# karmanDB_power.net
KiCad netlist of a schematic drawn in Altium Designer
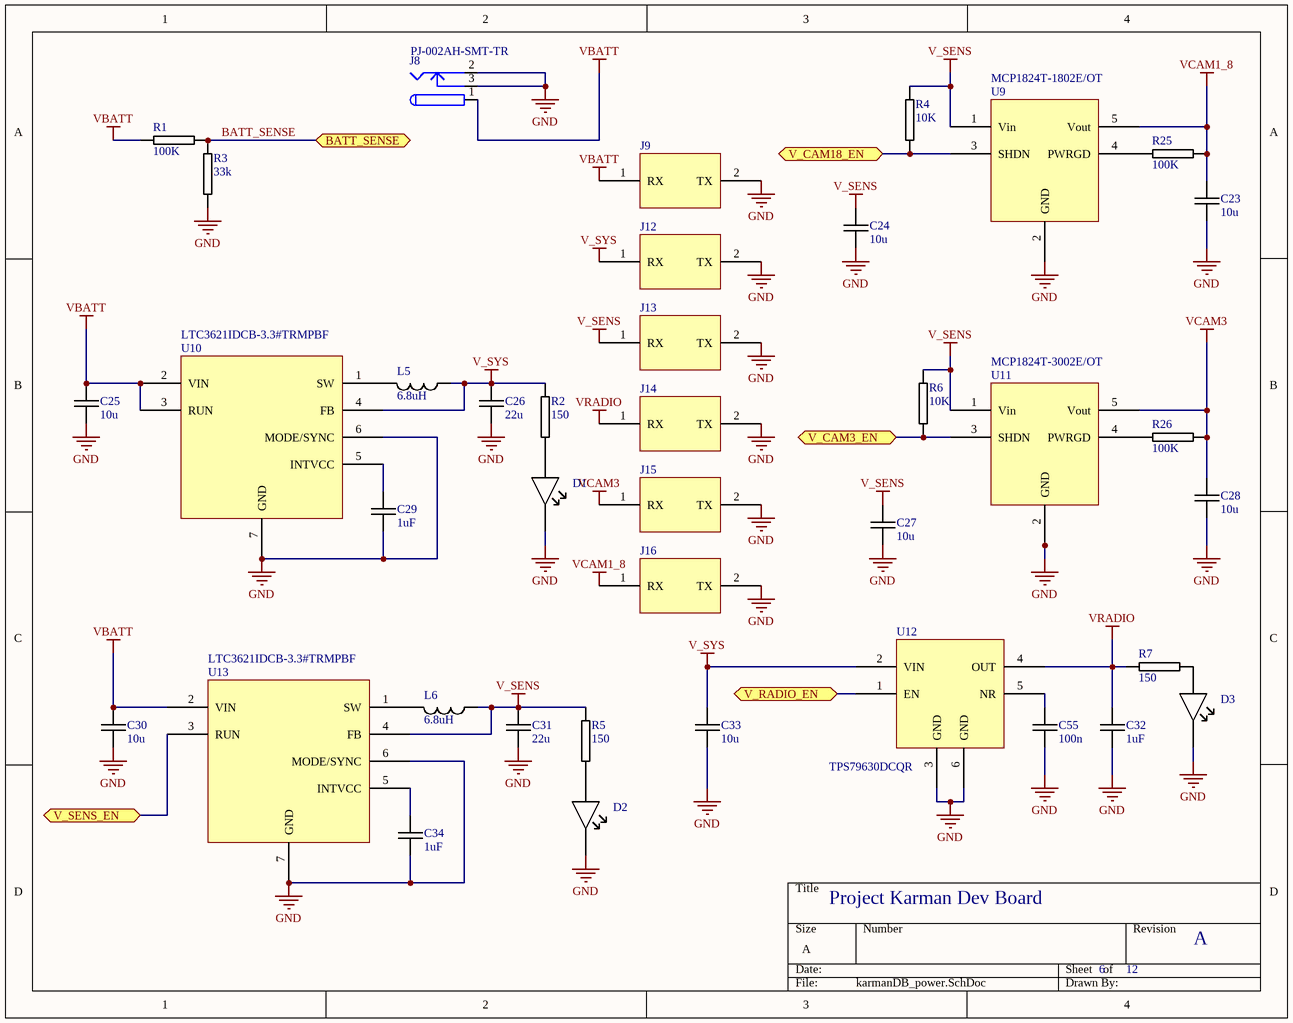
[diagram p0: karmanDB_power.SchDoc]

(export (version "E")
  (design (tool "Eeschema 10.0.6"))
  (components
    (comp (ref "C23")
      (value "10u")
      (footprint "MURATA_GRM_0603")
      (description "CAP CER 10UF 6.3V 20% X5R 0603")
      (fields
        (field (name "MANUFACTURER") "Murata Electronics North America")
        (field (name "MANUFACTURER PART NUMBER") "GRM188R60J106ME47J")
      )
      (libsource (lib "project_symbols") (part "CAP_MURATA_GRM188R60J106"))
    )
    (comp (ref "C24")
      (value "10u")
      (footprint "MURATA_GRM_0603")
      (description "CAP CER 10UF 6.3V 20% X5R 0603")
      (fields
        (field (name "MANUFACTURER") "Murata Electronics North America")
        (field (name "MANUFACTURER PART NUMBER") "GRM188R60J106ME47J")
      )
      (libsource (lib "project_symbols") (part "CAP_MURATA_GRM188R60J106"))
    )
    (comp (ref "C25")
      (value "10u")
      (footprint "MURATA_GRM_0603")
      (description "CAP CER 10UF 6.3V 20% X5R 0603")
      (fields
        (field (name "MANUFACTURER") "Murata Electronics North America")
        (field (name "MANUFACTURER PART NUMBER") "GRM188R60J106ME47J")
      )
      (libsource (lib "project_symbols") (part "CAP_MURATA_GRM188R60J106"))
    )
    (comp (ref "C26")
      (value "22u")
      (footprint "MURATA_GRM_0603")
      (description "CAP CER 22UF 10V 20% X5R 0603")
      (fields
        (field (name "MANUFACTURER") "Murata Electronics North America")
        (field (name "MANUFACTURER PART NUMBER") "GRM188R61A226ME15D")
      )
      (libsource (lib "project_symbols") (part "CAP_MURATA_GRM188R61A226ME15D"))
    )
    (comp (ref "C27")
      (value "10u")
      (footprint "MURATA_GRM_0603")
      (description "CAP CER 10UF 6.3V 20% X5R 0603")
      (fields
        (field (name "MANUFACTURER") "Murata Electronics North America")
        (field (name "MANUFACTURER PART NUMBER") "GRM188R60J106ME47J")
      )
      (libsource (lib "project_symbols") (part "CAP_MURATA_GRM188R60J106"))
    )
    (comp (ref "C28")
      (value "10u")
      (footprint "MURATA_GRM_0603")
      (description "CAP CER 10UF 6.3V 20% X5R 0603")
      (fields
        (field (name "MANUFACTURER") "Murata Electronics North America")
        (field (name "MANUFACTURER PART NUMBER") "GRM188R60J106ME47J")
      )
      (libsource (lib "project_symbols") (part "CAP_MURATA_GRM188R60J106"))
    )
    (comp (ref "C29")
      (value "1uF")
      (footprint "MURATA_GRM_0402")
      (description "CAP CER 1uF 10volts X5R 10% 0402")
      (fields
        (field (name "MANUFACTURER") "Murata Electronics")
        (field (name "MANUFACTURER PART NUMBER") "GRM155R61A105KE15D")
      )
      (libsource (lib "project_symbols") (part "CAP_MURATA_GRM155R61A105KE15D"))
    )
    (comp (ref "C30")
      (value "10u")
      (footprint "MURATA_GRM_0603")
      (description "CAP CER 10UF 6.3V 20% X5R 0603")
      (fields
        (field (name "MANUFACTURER") "Murata Electronics North America")
        (field (name "MANUFACTURER PART NUMBER") "GRM188R60J106ME47J")
      )
      (libsource (lib "project_symbols") (part "CAP_MURATA_GRM188R60J106"))
    )
    (comp (ref "C31")
      (value "22u")
      (footprint "MURATA_GRM_0603")
      (description "CAP CER 22UF 10V 20% X5R 0603")
      (fields
        (field (name "MANUFACTURER") "Murata Electronics North America")
        (field (name "MANUFACTURER PART NUMBER") "GRM188R61A226ME15D")
      )
      (libsource (lib "project_symbols") (part "CAP_MURATA_GRM188R61A226ME15D"))
    )
    (comp (ref "C32")
      (value "1uF")
      (footprint "MURATA_GRM_0402")
      (description "CAP CER 1uF 10volts X5R 10% 0402")
      (fields
        (field (name "MANUFACTURER") "Murata Electronics")
        (field (name "MANUFACTURER PART NUMBER") "GRM155R61A105KE15D")
      )
      (libsource (lib "project_symbols") (part "CAP_MURATA_GRM155R61A105KE15D"))
    )
    (comp (ref "C33")
      (value "10u")
      (footprint "MURATA_GRM_0603")
      (description "CAP CER 10UF 6.3V 20% X5R 0603")
      (fields
        (field (name "MANUFACTURER") "Murata Electronics North America")
        (field (name "MANUFACTURER PART NUMBER") "GRM188R60J106ME47J")
      )
      (libsource (lib "project_symbols") (part "CAP_MURATA_GRM188R60J106"))
    )
    (comp (ref "C34")
      (value "1uF")
      (footprint "MURATA_GRM_0402")
      (description "CAP CER 1uF 10volts X5R 10% 0402")
      (fields
        (field (name "MANUFACTURER") "Murata Electronics")
        (field (name "MANUFACTURER PART NUMBER") "GRM155R61A105KE15D")
      )
      (libsource (lib "project_symbols") (part "CAP_MURATA_GRM155R61A105KE15D"))
    )
    (comp (ref "C55")
      (value "100n")
      (footprint "MURATA_GRM_0603")
      (description "CAP CER 0.1UF 6.3V 10% X7R 0603")
      (fields
        (field (name "MANUFACTURER") "Murata Electronics North America")
        (field (name "MANUFACTURER PART NUMBER") "GRM188R70J104KA01D")
      )
      (libsource (lib "project_symbols") (part "CAP_MURATA_GRM188R70J104KA01D"))
    )
    (comp (ref "D1")
      (value "LED_LITEON_LTST-C150CKT")
      (footprint "LITEON_LTST-C150")
      (description "LED RED CLEAR 1206 SMD")
      (fields
        (field (name "MANUFACTURER") "Lite-On Inc")
        (field (name "MANUFACTURER PART NUMBER") "LTST-C150CKT")
      )
      (libsource (lib "project_symbols") (part "LED_LITEON_LTST-C150CKT"))
    )
    (comp (ref "D2")
      (value "LED_LITEON_LTST-C150CKT")
      (footprint "LITEON_LTST-C150")
      (description "LED RED CLEAR 1206 SMD")
      (fields
        (field (name "MANUFACTURER") "Lite-On Inc")
        (field (name "MANUFACTURER PART NUMBER") "LTST-C150CKT")
      )
      (libsource (lib "project_symbols") (part "LED_LITEON_LTST-C150CKT"))
    )
    (comp (ref "D3")
      (value "LED_LITEON_LTST-C150CKT")
      (footprint "LITEON_LTST-C150")
      (description "LED RED CLEAR 1206 SMD")
      (fields
        (field (name "MANUFACTURER") "Lite-On Inc")
        (field (name "MANUFACTURER PART NUMBER") "LTST-C150CKT")
      )
      (libsource (lib "project_symbols") (part "LED_LITEON_LTST-C150CKT"))
    )
    (comp (ref "J8")
      (value "PJ-002AH-SMT-TR")
      (footprint "PJ-002AH-SMT")
      (description "CONN POWER JACK 2.1X5.5MM HI CUR")
      (fields (field (name "MANUFACTURER") "CUI Inc."))
      (libsource (lib "karman_pcb") (part "PJ-002AH-SMT-TR"))
    )
    (comp (ref "J9")
      (value "961102-6404-AR")
      (footprint "3M_961102-6X04")
      (description "CONN HEADER VERT SGL 2POS GOLD")
      (fields (field (name "MANUFACTURER") "3M"))
      (libsource (lib "karman_pcb") (part "961102-6404-AR"))
    )
    (comp (ref "J12")
      (value "961102-6404-AR")
      (footprint "3M_961102-6X04")
      (description "CONN HEADER VERT SGL 2POS GOLD")
      (fields (field (name "MANUFACTURER") "3M"))
      (libsource (lib "karman_pcb") (part "961102-6404-AR"))
    )
    (comp (ref "J13")
      (value "961102-6404-AR")
      (footprint "3M_961102-6X04")
      (description "CONN HEADER VERT SGL 2POS GOLD")
      (fields (field (name "MANUFACTURER") "3M"))
      (libsource (lib "karman_pcb") (part "961102-6404-AR"))
    )
    (comp (ref "J14")
      (value "961102-6404-AR")
      (footprint "3M_961102-6X04")
      (description "CONN HEADER VERT SGL 2POS GOLD")
      (fields (field (name "MANUFACTURER") "3M"))
      (libsource (lib "karman_pcb") (part "961102-6404-AR"))
    )
    (comp (ref "J15")
      (value "961102-6404-AR")
      (footprint "3M_961102-6X04")
      (description "CONN HEADER VERT SGL 2POS GOLD")
      (fields (field (name "MANUFACTURER") "3M"))
      (libsource (lib "karman_pcb") (part "961102-6404-AR"))
    )
    (comp (ref "J16")
      (value "961102-6404-AR")
      (footprint "3M_961102-6X04")
      (description "CONN HEADER VERT SGL 2POS GOLD")
      (fields (field (name "MANUFACTURER") "3M"))
      (libsource (lib "karman_pcb") (part "961102-6404-AR"))
    )
    (comp (ref "L5")
      (value "6.8uH")
      (footprint "TDK_RLF7030")
      (description "FIXED IND 6.8UH 2.8A 37.3 MOHM")
      (fields
        (field (name "MANUFACTURER") "TDK Corporation")
        (field (name "MANUFACTURER PART NUMBER") "RLF7030T-6R8M2R8")
      )
      (libsource (lib "project_symbols") (part "TDK_IND_RLF7030T-6R8M2R8"))
    )
    (comp (ref "L6")
      (value "6.8uH")
      (footprint "TDK_RLF7030")
      (description "FIXED IND 6.8UH 2.8A 37.3 MOHM")
      (fields
        (field (name "MANUFACTURER") "TDK Corporation")
        (field (name "MANUFACTURER PART NUMBER") "RLF7030T-6R8M2R8")
      )
      (libsource (lib "project_symbols") (part "TDK_IND_RLF7030T-6R8M2R8"))
    )
    (comp (ref "R1")
      (value "100K")
      (footprint "PANASONIC_ERJ3R")
      (description "RES SMD 100K OHM 5% 1/10W 0603")
      (fields
        (field (name "MANUFACTURER") "Panasonic Electronic Components")
        (field (name "MANUFACTURER PART NUMBER") "ERJ-3GEYJ104V")
      )
      (libsource (lib "project_symbols") (part "RES_PANASONIC_ERJ-3GEYJ104V"))
    )
    (comp (ref "R2")
      (value "150")
      (footprint "PANASONIC_ERJ3R")
      (description "RES SMD 150 OHM 5% 1/10W 0603")
      (fields
        (field (name "MANUFACTURER") "Panasonic Electronic Components")
        (field (name "MANUFACTURER PART NUMBER") "ERJ-3GEYJ151V")
      )
      (libsource (lib "project_symbols") (part "RES_PANASONIC_ERJ-3GEYJ151V"))
    )
    (comp (ref "R3")
      (value "33k")
      (footprint "PANASONIC_ERJ2R_SERIES")
      (description "RES SMD 33K OHM 5% 1/10W 0402")
      (fields
        (field (name "MANUFACTURER") "Panasonic Electronic Components")
        (field (name "MANUFACTURER PART NUMBER") "ERJ-2GEJ333X")
      )
      (libsource (lib "project_symbols") (part "RES_PANASONIC_ERJ-2GEJ333X"))
    )
    (comp (ref "R4")
      (value "10K")
      (footprint "PANASONIC_ERJ3R")
      (description "RES SMD 10K OHM 5% 1/10W 0603")
      (fields
        (field (name "MANUFACTURER") "Panasonic Electronic Components")
        (field (name "MANUFACTURER PART NUMBER") "ERJ-3GEYJ103V")
      )
      (libsource (lib "project_symbols") (part "RES_PANASONIC_ERJ-3GEYJ103V"))
    )
    (comp (ref "R5")
      (value "150")
      (footprint "PANASONIC_ERJ3R")
      (description "RES SMD 150 OHM 5% 1/10W 0603")
      (fields
        (field (name "MANUFACTURER") "Panasonic Electronic Components")
        (field (name "MANUFACTURER PART NUMBER") "ERJ-3GEYJ151V")
      )
      (libsource (lib "project_symbols") (part "RES_PANASONIC_ERJ-3GEYJ151V"))
    )
    (comp (ref "R6")
      (value "10K")
      (footprint "PANASONIC_ERJ3R")
      (description "RES SMD 10K OHM 5% 1/10W 0603")
      (fields
        (field (name "MANUFACTURER") "Panasonic Electronic Components")
        (field (name "MANUFACTURER PART NUMBER") "ERJ-3GEYJ103V")
      )
      (libsource (lib "project_symbols") (part "RES_PANASONIC_ERJ-3GEYJ103V"))
    )
    (comp (ref "R7")
      (value "150")
      (footprint "PANASONIC_ERJ3R")
      (description "RES SMD 150 OHM 5% 1/10W 0603")
      (fields
        (field (name "MANUFACTURER") "Panasonic Electronic Components")
        (field (name "MANUFACTURER PART NUMBER") "ERJ-3GEYJ151V")
      )
      (libsource (lib "project_symbols") (part "RES_PANASONIC_ERJ-3GEYJ151V"))
    )
    (comp (ref "R25")
      (value "100K")
      (footprint "PANASONIC_ERJ3R")
      (description "RES SMD 100K OHM 5% 1/10W 0603")
      (fields
        (field (name "MANUFACTURER") "Panasonic Electronic Components")
        (field (name "MANUFACTURER PART NUMBER") "ERJ-3GEYJ104V")
      )
      (libsource (lib "project_symbols") (part "RES_PANASONIC_ERJ-3GEYJ104V"))
    )
    (comp (ref "R26")
      (value "100K")
      (footprint "PANASONIC_ERJ3R")
      (description "RES SMD 100K OHM 5% 1/10W 0603")
      (fields
        (field (name "MANUFACTURER") "Panasonic Electronic Components")
        (field (name "MANUFACTURER PART NUMBER") "ERJ-3GEYJ104V")
      )
      (libsource (lib "project_symbols") (part "RES_PANASONIC_ERJ-3GEYJ104V"))
    )
    (comp (ref "U9")
      (value "MCP1824T-1802E/OT")
      (footprint "26-27 MCP1824T(-3002E/OT)(-1802E/OT)")
      (description "IC REG LDO 1.8V 0.3A SOT23-5")
      (fields (field (name "MANUFACTURER") "Microchip Technology"))
      (libsource (lib "karman_pcb") (part "MCP1824T-1802E/OT"))
    )
    (comp (ref "U10")
      (value "LTC3621IDCB-3.3#TRMPBF")
      (footprint "29 LTC3621IDCB-3.3")
      (description "IC REG BUCK 3.3V 1A SYNC 6DFN")
      (fields (field (name "MANUFACTURER") "Linear Technology"))
      (libsource (lib "karman_pcb") (part "LTC3621IDCB-3.3#TRMPBF"))
    )
    (comp (ref "U11")
      (value "MCP1824T-3002E/OT")
      (footprint "26-27 MCP1824T(-3002E/OT)(-1802E/OT)")
      (description "IC REG LDO 3V 0.3A SOT23-5")
      (fields (field (name "MANUFACTURER") "Microchip Technology"))
      (libsource (lib "karman_pcb") (part "MCP1824T-3002E/OT"))
    )
    (comp (ref "U12")
      (value "TPS79630DCQR")
      (footprint "TPS79630")
      (description "IC REG LDO 3V 1A SOT223-6")
      (fields (field (name "MANUFACTURER") "Texas Instruments"))
      (libsource (lib "karman_pcb") (part "TPS79630DCQR"))
    )
    (comp (ref "U13")
      (value "LTC3621IDCB-3.3#TRMPBF")
      (footprint "29 LTC3621IDCB-3.3")
      (description "IC REG BUCK 3.3V 1A SYNC 6DFN")
      (fields (field (name "MANUFACTURER") "Linear Technology"))
      (libsource (lib "karman_pcb") (part "LTC3621IDCB-3.3#TRMPBF"))
    )
  )
  (nets
    (net (code "1") (name "/BATT_SENSE") (class "Default")
      (node (ref "R1") (pin "2") (pintype "passive"))
      (node (ref "R3") (pin "1") (pintype "passive"))
    )
    (net (code "2") (name "/V_CAM3_EN") (class "Default")
      (node (ref "R6") (pin "2") (pintype "passive"))
      (node (ref "U11") (pin "3") (pinfunction "SHDN_3") (pintype "passive"))
    )
    (net (code "3") (name "/V_CAM18_EN") (class "Default")
      (node (ref "R4") (pin "2") (pintype "passive"))
      (node (ref "U9") (pin "3") (pinfunction "SHDN_3") (pintype "passive"))
    )
    (net (code "4") (name "/V_RADIO_EN") (class "Default")
      (node (ref "U12") (pin "1") (pinfunction "EN_1") (pintype "passive"))
    )
    (net (code "5") (name "/V_SENS_EN") (class "Default")
      (node (ref "U13") (pin "3") (pinfunction "RUN_3") (pintype "passive"))
    )
    (net (code "6") (name "GND") (class "Default")
      (node (ref "C23") (pin "2") (pintype "passive"))
      (node (ref "C24") (pin "2") (pintype "passive"))
      (node (ref "C25") (pin "2") (pintype "passive"))
      (node (ref "C26") (pin "2") (pintype "passive"))
      (node (ref "C27") (pin "2") (pintype "passive"))
      (node (ref "C28") (pin "2") (pintype "passive"))
      (node (ref "C29") (pin "2") (pintype "passive"))
      (node (ref "C30") (pin "2") (pintype "passive"))
      (node (ref "C31") (pin "2") (pintype "passive"))
      (node (ref "C32") (pin "2") (pintype "passive"))
      (node (ref "C33") (pin "2") (pintype "passive"))
      (node (ref "C34") (pin "2") (pintype "passive"))
      (node (ref "C55") (pin "2") (pintype "passive"))
      (node (ref "D1") (pin "K") (pintype "passive"))
      (node (ref "D2") (pin "K") (pintype "passive"))
      (node (ref "D3") (pin "K") (pintype "passive"))
      (node (ref "J12") (pin "2") (pinfunction "TX_2") (pintype "passive"))
      (node (ref "J13") (pin "2") (pinfunction "TX_2") (pintype "passive"))
      (node (ref "J14") (pin "2") (pinfunction "TX_2") (pintype "passive"))
      (node (ref "J15") (pin "2") (pinfunction "TX_2") (pintype "passive"))
      (node (ref "J16") (pin "2") (pinfunction "TX_2") (pintype "passive"))
      (node (ref "J8") (pin "2") (pinfunction "2_2") (pintype "power_in"))
      (node (ref "J8") (pin "3") (pinfunction "3_3") (pintype "power_in"))
      (node (ref "J9") (pin "2") (pinfunction "TX_2") (pintype "passive"))
      (node (ref "R3") (pin "2") (pintype "passive"))
      (node (ref "U10") (pin "6") (pinfunction "MODE/SYNC_6") (pintype "passive"))
      (node (ref "U10") (pin "7") (pinfunction "GND_7") (pintype "passive"))
      (node (ref "U11") (pin "2") (pinfunction "GND_2") (pintype "passive"))
      (node (ref "U12") (pin "3") (pinfunction "GND_3") (pintype "passive"))
      (node (ref "U12") (pin "6") (pinfunction "GND_6") (pintype "passive"))
      (node (ref "U13") (pin "6") (pinfunction "MODE/SYNC_6") (pintype "passive"))
      (node (ref "U13") (pin "7") (pinfunction "GND_7") (pintype "passive"))
      (node (ref "U9") (pin "2") (pinfunction "GND_2") (pintype "passive"))
    )
    (net (code "7") (name "Net-(D1-PadA)") (class "Default")
      (node (ref "D1") (pin "A") (pintype "passive"))
      (node (ref "R2") (pin "1") (pintype "passive"))
    )
    (net (code "8") (name "Net-(D2-PadA)") (class "Default")
      (node (ref "D2") (pin "A") (pintype "passive"))
      (node (ref "R5") (pin "2") (pintype "passive"))
    )
    (net (code "9") (name "Net-(D3-PadA)") (class "Default")
      (node (ref "D3") (pin "A") (pintype "passive"))
      (node (ref "R7") (pin "2") (pintype "passive"))
    )
    (net (code "10") (name "Net-(U9-PWRGD)") (class "Default")
      (node (ref "R25") (pin "1") (pintype "passive"))
      (node (ref "U9") (pin "4") (pinfunction "PWRGD_4") (pintype "passive"))
    )
    (net (code "11") (name "Net-(U10-INTVCC)") (class "Default")
      (node (ref "C29") (pin "1") (pintype "passive"))
      (node (ref "U10") (pin "5") (pinfunction "INTVCC_5") (pintype "passive"))
    )
    (net (code "12") (name "Net-(U10-SW)") (class "Default")
      (node (ref "L5") (pin "2") (pinfunction "2_2") (pintype "passive"))
      (node (ref "U10") (pin "1") (pinfunction "SW_1") (pintype "passive"))
    )
    (net (code "13") (name "Net-(U11-PWRGD)") (class "Default")
      (node (ref "R26") (pin "1") (pintype "passive"))
      (node (ref "U11") (pin "4") (pinfunction "PWRGD_4") (pintype "passive"))
    )
    (net (code "14") (name "Net-(U12-NR)") (class "Default")
      (node (ref "C55") (pin "1") (pintype "passive"))
      (node (ref "U12") (pin "5") (pinfunction "NR_5") (pintype "passive"))
    )
    (net (code "15") (name "Net-(U13-INTVCC)") (class "Default")
      (node (ref "C34") (pin "1") (pintype "passive"))
      (node (ref "U13") (pin "5") (pinfunction "INTVCC_5") (pintype "passive"))
    )
    (net (code "16") (name "Net-(U13-SW)") (class "Default")
      (node (ref "L6") (pin "2") (pinfunction "2_2") (pintype "passive"))
      (node (ref "U13") (pin "1") (pinfunction "SW_1") (pintype "passive"))
    )
    (net (code "17") (name "VBATT") (class "Default")
      (node (ref "C25") (pin "1") (pintype "passive"))
      (node (ref "C30") (pin "1") (pintype "passive"))
      (node (ref "J8") (pin "1") (pinfunction "1_1") (pintype "power_in"))
      (node (ref "J9") (pin "1") (pinfunction "RX_1") (pintype "passive"))
      (node (ref "R1") (pin "1") (pintype "passive"))
      (node (ref "U10") (pin "2") (pinfunction "VIN_2") (pintype "passive"))
      (node (ref "U10") (pin "3") (pinfunction "RUN_3") (pintype "passive"))
      (node (ref "U13") (pin "2") (pinfunction "VIN_2") (pintype "passive"))
    )
    (net (code "18") (name "VCAM1_8") (class "Default")
      (node (ref "C23") (pin "1") (pintype "passive"))
      (node (ref "J16") (pin "1") (pinfunction "RX_1") (pintype "passive"))
      (node (ref "R25") (pin "2") (pintype "passive"))
      (node (ref "U9") (pin "5") (pinfunction "Vout_5") (pintype "passive"))
    )
    (net (code "19") (name "VCAM3") (class "Default")
      (node (ref "C28") (pin "1") (pintype "passive"))
      (node (ref "J15") (pin "1") (pinfunction "RX_1") (pintype "passive"))
      (node (ref "R26") (pin "2") (pintype "passive"))
      (node (ref "U11") (pin "5") (pinfunction "Vout_5") (pintype "passive"))
    )
    (net (code "20") (name "VRADIO") (class "Default")
      (node (ref "C32") (pin "1") (pintype "passive"))
      (node (ref "J14") (pin "1") (pinfunction "RX_1") (pintype "passive"))
      (node (ref "R7") (pin "1") (pintype "passive"))
      (node (ref "U12") (pin "4") (pinfunction "OUT_4") (pintype "passive"))
    )
    (net (code "21") (name "V_SENS") (class "Default")
      (node (ref "C24") (pin "1") (pintype "passive"))
      (node (ref "C27") (pin "1") (pintype "passive"))
      (node (ref "C31") (pin "1") (pintype "passive"))
      (node (ref "J13") (pin "1") (pinfunction "RX_1") (pintype "passive"))
      (node (ref "L6") (pin "1") (pinfunction "1_1") (pintype "passive"))
      (node (ref "R4") (pin "1") (pintype "passive"))
      (node (ref "R5") (pin "1") (pintype "passive"))
      (node (ref "R6") (pin "1") (pintype "passive"))
      (node (ref "U11") (pin "1") (pinfunction "Vin_1") (pintype "passive"))
      (node (ref "U13") (pin "4") (pinfunction "FB_4") (pintype "passive"))
      (node (ref "U9") (pin "1") (pinfunction "Vin_1") (pintype "passive"))
    )
    (net (code "22") (name "V_SYS") (class "Default")
      (node (ref "C26") (pin "1") (pintype "passive"))
      (node (ref "C33") (pin "1") (pintype "passive"))
      (node (ref "J12") (pin "1") (pinfunction "RX_1") (pintype "passive"))
      (node (ref "L5") (pin "1") (pinfunction "1_1") (pintype "passive"))
      (node (ref "R2") (pin "2") (pintype "passive"))
      (node (ref "U10") (pin "4") (pinfunction "FB_4") (pintype "passive"))
      (node (ref "U12") (pin "2") (pinfunction "VIN_2") (pintype "passive"))
    )
  )
)
